# soundsensor.net
KiCad netlist of a schematic drawn in EAGLE
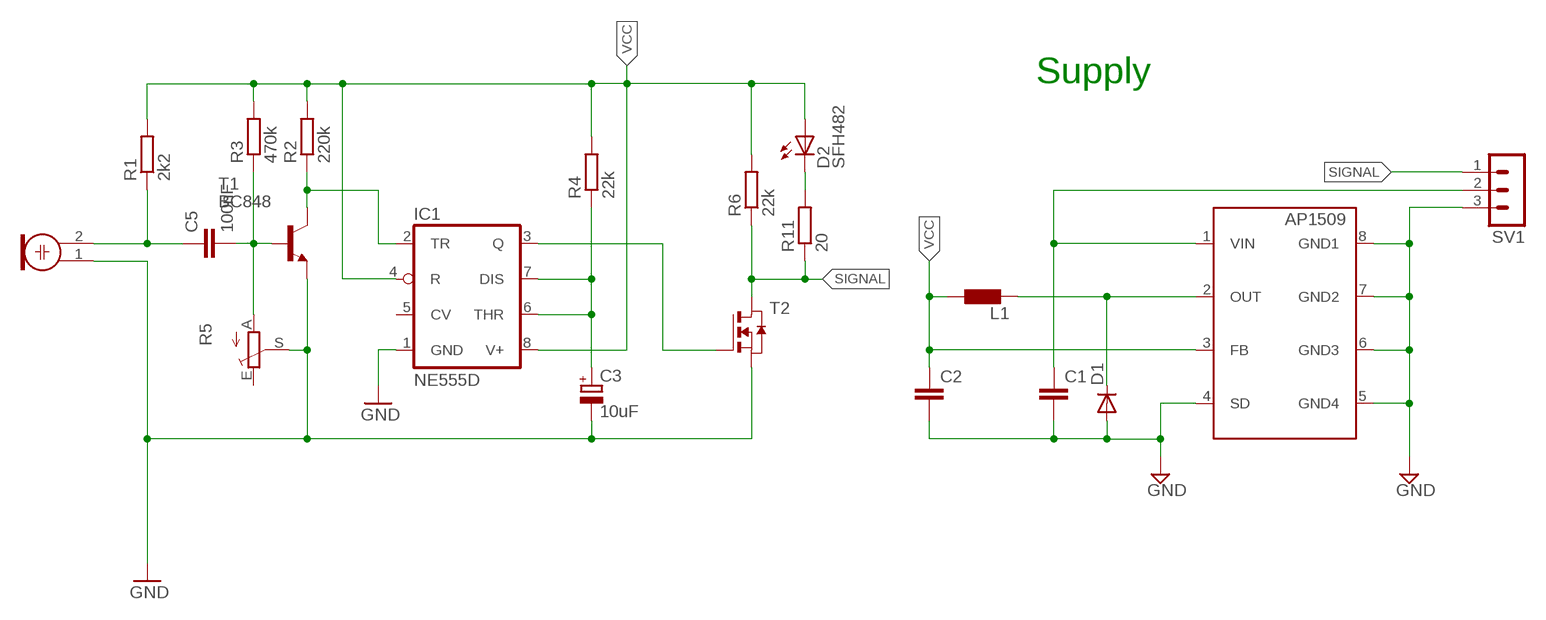
[diagram p0: schematic, sheet 1]

(export (version "E")
  (design (tool "Eeschema 10.0.6"))
  (components
    (comp (ref "C1")
      (value "C-EUC1210")
      (footprint "eagle-import:C1210")
      (libsource (lib "eagle-import") (part "C-EUC1210"))
    )
    (comp (ref "C2")
      (value "C-EUC1210")
      (footprint "eagle-import:C1210")
      (libsource (lib "eagle-import") (part "C-EUC1210"))
    )
    (comp (ref "C3")
      (value "10uF")
      (footprint "eagle-import:150CLZ-1010")
      (libsource (lib "eagle-import") (part "CPOL-EU150CLZ-1010"))
    )
    (comp (ref "C5")
      (value "100nF")
      (footprint "eagle-import:C0805K")
      (libsource (lib "eagle-import") (part "C-EUC0805K"))
    )
    (comp (ref "D1")
      (value "DIODE-SOD323-W")
      (footprint "eagle-import:SOD323-W")
      (libsource (lib "eagle-import") (part "DIODE-SOD323-W"))
    )
    (comp (ref "D2")
      (value "SFH482")
      (footprint "eagle-import:SFH482")
      (libsource (lib "eagle-import") (part "SFH482"))
    )
    (comp (ref "IC1")
      (value "NE555D")
      (footprint "eagle-import:SO08")
      (libsource (lib "eagle-import") (part "555DNE"))
    )
    (comp (ref "L1")
      (value "LL5038P")
      (footprint "eagle-import:L5038P")
      (libsource (lib "eagle-import") (part "LL5038P"))
    )
    (comp (ref "M1")
      (value "ELECTRET_MICROPHON-WM-61A")
      (footprint "eagle-import:WM-61A")
      (libsource (lib "eagle-import") (part "ELECTRET_MICROPHON-WM-61A"))
    )
    (comp (ref "R1")
      (value "2k2")
      (footprint "eagle-import:M0805")
      (libsource (lib "eagle-import") (part "R-EU_M0805"))
    )
    (comp (ref "R2")
      (value "220k")
      (footprint "eagle-import:M0805")
      (libsource (lib "eagle-import") (part "R-EU_M0805"))
    )
    (comp (ref "R3")
      (value "470k")
      (footprint "eagle-import:M0805")
      (libsource (lib "eagle-import") (part "R-EU_M0805"))
    )
    (comp (ref "R4")
      (value "22k")
      (footprint "eagle-import:M0805")
      (libsource (lib "eagle-import") (part "R-EU_M0805"))
    )
    (comp (ref "R5")
      (value "TRIM_EU-CA9V")
      (footprint "eagle-import:CA9V")
      (libsource (lib "eagle-import") (part "TRIM_EU-CA9V"))
    )
    (comp (ref "R6")
      (value "22k")
      (footprint "eagle-import:M0805")
      (libsource (lib "eagle-import") (part "R-EU_M0805"))
    )
    (comp (ref "R11")
      (value "20")
      (footprint "eagle-import:M0805")
      (libsource (lib "eagle-import") (part "R-EU_M0805"))
    )
    (comp (ref "SV1")
      (value "MA03-1")
      (footprint "eagle-import:MA03-1")
      (libsource (lib "eagle-import") (part "MA03-1"))
    )
    (comp (ref "T1")
      (value "BC848")
      (footprint "eagle-import:SOT23")
      (libsource (lib "eagle-import") (part "BC848"))
    )
    (comp (ref "T2")
      (value "NMOSSOT23")
      (footprint "eagle-import:SOT-23")
      (libsource (lib "eagle-import") (part "NMOSSOT23"))
    )
    (comp (ref "U$1")
      (value "AP1509")
      (footprint "eagle-import:SOP08")
      (libsource (lib "eagle-import") (part "AP1509"))
    )
  )
  (nets
    (net (code "1") (name "GND") (class "Default")
      (node (ref "C1") (pin "2") (pinfunction "2_2") (pintype "passive"))
      (node (ref "C2") (pin "2") (pinfunction "2_2") (pintype "passive"))
      (node (ref "C3") (pin "-") (pinfunction "-_-") (pintype "passive"))
      (node (ref "D1") (pin "A") (pinfunction "A_A") (pintype "passive"))
      (node (ref "IC1") (pin "1") (pinfunction "GND_1") (pintype "power_in"))
      (node (ref "M1") (pin "1") (pinfunction "1_1") (pintype "passive"))
      (node (ref "R5") (pin "S") (pinfunction "S_S") (pintype "passive"))
      (node (ref "SV1") (pin "3") (pinfunction "3_3") (pintype "passive"))
      (node (ref "T1") (pin "2") (pinfunction "E_2") (pintype "passive"))
      (node (ref "T2") (pin "2") (pinfunction "S_2") (pintype "passive"))
      (node (ref "U$1") (pin "4") (pinfunction "SD_4") (pintype "bidirectional"))
      (node (ref "U$1") (pin "5") (pinfunction "GND4_5") (pintype "bidirectional"))
      (node (ref "U$1") (pin "6") (pinfunction "GND3_6") (pintype "bidirectional"))
      (node (ref "U$1") (pin "7") (pinfunction "GND2_7") (pintype "bidirectional"))
      (node (ref "U$1") (pin "8") (pinfunction "GND1_8") (pintype "bidirectional"))
    )
    (net (code "2") (name "Net-(C5-Pad1)") (class "Default")
      (node (ref "C5") (pin "1") (pinfunction "1_1") (pintype "passive"))
      (node (ref "M1") (pin "2") (pinfunction "2_2") (pintype "passive"))
      (node (ref "R1") (pin "1") (pinfunction "1_1") (pintype "passive"))
    )
    (net (code "3") (name "Net-(D2-C)") (class "Default")
      (node (ref "D2") (pin "K") (pinfunction "C_K") (pintype "passive"))
      (node (ref "R11") (pin "2") (pinfunction "2_2") (pintype "passive"))
    )
    (net (code "4") (name "Net-(IC1-DIS)") (class "Default")
      (node (ref "C3") (pin "+") (pinfunction "+_+") (pintype "passive"))
      (node (ref "IC1") (pin "6") (pinfunction "THR_6") (pintype "input"))
      (node (ref "IC1") (pin "7") (pinfunction "DIS_7") (pintype "input"))
      (node (ref "R4") (pin "1") (pinfunction "1_1") (pintype "passive"))
    )
    (net (code "5") (name "Net-(IC1-Q)") (class "Default")
      (node (ref "IC1") (pin "3") (pinfunction "Q_3") (pintype "output"))
      (node (ref "T2") (pin "3") (pinfunction "G_3") (pintype "passive"))
    )
    (net (code "6") (name "Net-(IC1-TR)") (class "Default")
      (node (ref "IC1") (pin "2") (pinfunction "TR_2") (pintype "input"))
      (node (ref "R2") (pin "1") (pinfunction "1_1") (pintype "passive"))
      (node (ref "T1") (pin "3") (pinfunction "C_3") (pintype "passive"))
    )
    (net (code "7") (name "Net-(T1-B)") (class "Default")
      (node (ref "C5") (pin "2") (pinfunction "2_2") (pintype "passive"))
      (node (ref "R3") (pin "1") (pinfunction "1_1") (pintype "passive"))
      (node (ref "R5") (pin "A") (pinfunction "A_A") (pintype "passive"))
      (node (ref "T1") (pin "1") (pinfunction "B_1") (pintype "passive"))
    )
    (net (code "8") (name "Net-(U$1-OUT)") (class "Default")
      (node (ref "D1") (pin "C") (pinfunction "C_C") (pintype "passive"))
      (node (ref "L1") (pin "2") (pinfunction "2_2") (pintype "passive"))
      (node (ref "U$1") (pin "2") (pinfunction "OUT_2") (pintype "bidirectional"))
    )
    (net (code "9") (name "Net-(U$1-VIN)") (class "Default")
      (node (ref "C1") (pin "1") (pinfunction "1_1") (pintype "passive"))
      (node (ref "SV1") (pin "2") (pinfunction "2_2") (pintype "passive"))
      (node (ref "U$1") (pin "1") (pinfunction "VIN_1") (pintype "bidirectional"))
    )
    (net (code "10") (name "SIGNAL") (class "Default")
      (node (ref "R11") (pin "1") (pinfunction "1_1") (pintype "passive"))
      (node (ref "R6") (pin "1") (pinfunction "1_1") (pintype "passive"))
      (node (ref "SV1") (pin "1") (pinfunction "1_1") (pintype "passive"))
      (node (ref "T2") (pin "1") (pinfunction "D_1") (pintype "passive"))
    )
    (net (code "11") (name "VCC") (class "Default")
      (node (ref "C2") (pin "1") (pinfunction "1_1") (pintype "passive"))
      (node (ref "D2") (pin "A") (pinfunction "A_A") (pintype "passive"))
      (node (ref "IC1") (pin "4") (pinfunction "R_4") (pintype "input"))
      (node (ref "IC1") (pin "8") (pinfunction "V+_8") (pintype "power_in"))
      (node (ref "L1") (pin "1") (pinfunction "1_1") (pintype "passive"))
      (node (ref "R1") (pin "2") (pinfunction "2_2") (pintype "passive"))
      (node (ref "R2") (pin "2") (pinfunction "2_2") (pintype "passive"))
      (node (ref "R3") (pin "2") (pinfunction "2_2") (pintype "passive"))
      (node (ref "R4") (pin "2") (pinfunction "2_2") (pintype "passive"))
      (node (ref "R6") (pin "2") (pinfunction "2_2") (pintype "passive"))
      (node (ref "U$1") (pin "3") (pinfunction "FB_3") (pintype "bidirectional"))
    )
    (net (code "12") (name "unconnected-(IC1-CV-Pad5)") (class "Default")
      (node (ref "IC1") (pin "5") (pinfunction "CV_5") (pintype "input"))
    )
    (net (code "13") (name "unconnected-(R5-PadE)") (class "Default")
      (node (ref "R5") (pin "E") (pinfunction "E_E") (pintype "passive"))
    )
  )
)
